# photodiode_front.net
KiCad netlist of a schematic drawn in EAGLE
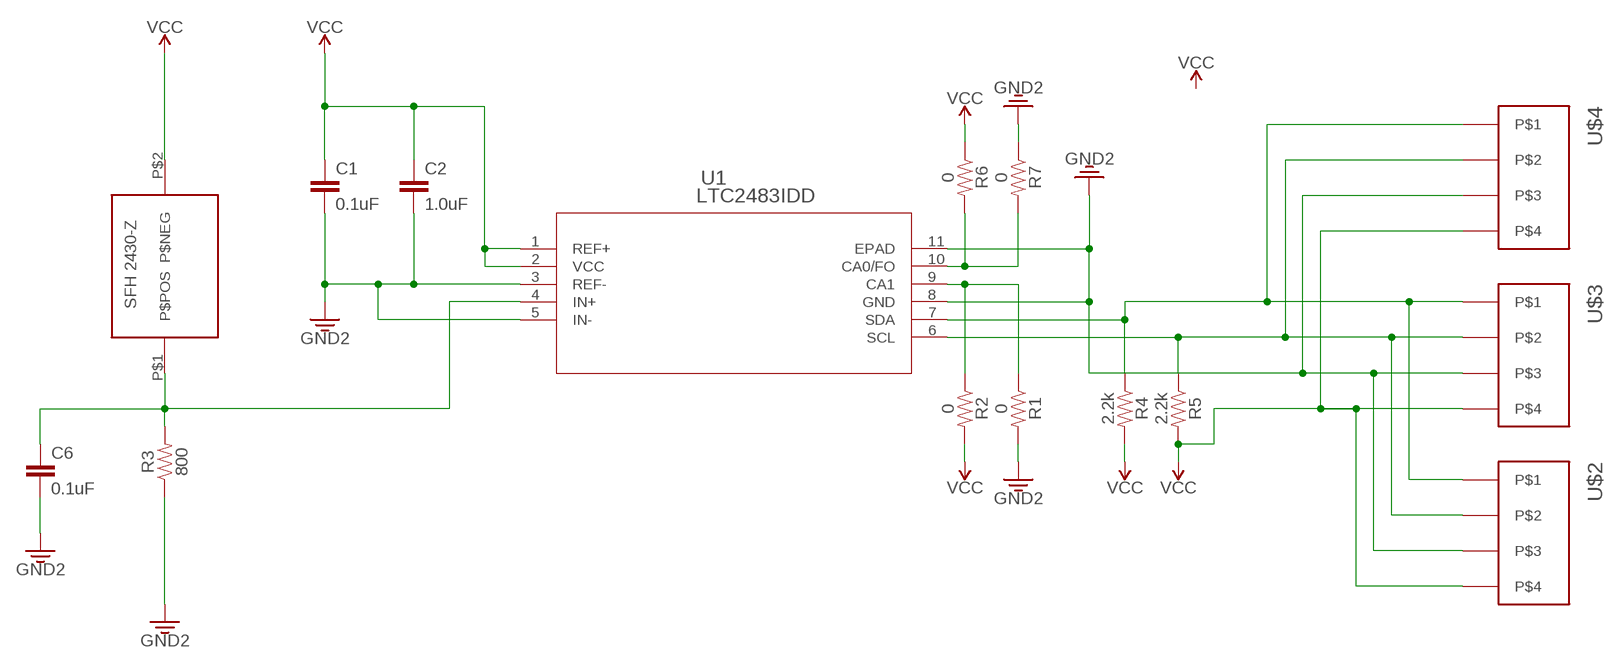
[diagram p0: schematic, sheet 1]

(export (version "E")
  (design (tool "Eeschema 10.0.6"))
  (components
    (comp (ref "C1")
      (value "0.1uF")
      (footprint "eagle-import:0805")
      (libsource (lib "eagle-import") (part "10UF-0805-10V-10%"))
    )
    (comp (ref "C2")
      (value "1.0uF")
      (footprint "eagle-import:0805")
      (libsource (lib "eagle-import") (part "10UF-0805-10V-10%"))
    )
    (comp (ref "C6")
      (value "0.1uF")
      (footprint "eagle-import:0805")
      (libsource (lib "eagle-import") (part "10UF-0805-10V-10%"))
    )
    (comp (ref "R1")
      (value "0")
      (footprint "eagle-import:0805")
      (libsource (lib "eagle-import") (part "RESISTOR0805"))
    )
    (comp (ref "R2")
      (value "0")
      (footprint "eagle-import:0805")
      (libsource (lib "eagle-import") (part "RESISTOR0805"))
    )
    (comp (ref "R3")
      (value "800")
      (footprint "eagle-import:0805")
      (libsource (lib "eagle-import") (part "RESISTOR0805"))
    )
    (comp (ref "R4")
      (value "2.2k")
      (footprint "eagle-import:0805")
      (libsource (lib "eagle-import") (part "RESISTOR0805"))
    )
    (comp (ref "R5")
      (value "2.2k")
      (footprint "eagle-import:0805")
      (libsource (lib "eagle-import") (part "RESISTOR0805"))
    )
    (comp (ref "R6")
      (value "0")
      (footprint "eagle-import:0805")
      (libsource (lib "eagle-import") (part "RESISTOR0805"))
    )
    (comp (ref "R7")
      (value "0")
      (footprint "eagle-import:0805")
      (libsource (lib "eagle-import") (part "RESISTOR0805"))
    )
    (comp (ref "U$1")
      (value "SFH-2430-Z")
      (footprint "eagle-import:DIL")
      (libsource (lib "eagle-import") (part "SFH-2430-Z"))
    )
    (comp (ref "U$2")
      (value "PICOLOCK_4PICOLOCK_4")
      (footprint "eagle-import:PICOLOCK_4")
      (libsource (lib "eagle-import") (part "PICOLOCK_4PICOLOCK_4"))
    )
    (comp (ref "U$3")
      (value "PICOLOCK_4PICOLOCK_4")
      (footprint "eagle-import:PICOLOCK_4")
      (libsource (lib "eagle-import") (part "PICOLOCK_4PICOLOCK_4"))
    )
    (comp (ref "U$4")
      (value "PICOLOCK_4PICOLOCK_4")
      (footprint "eagle-import:PICOLOCK_4")
      (libsource (lib "eagle-import") (part "PICOLOCK_4PICOLOCK_4"))
    )
    (comp (ref "U1")
      (value "LTC2483IDD")
      (footprint "eagle-import:DFN-10_DD")
      (fields (field (name "MANUFACTURER_PART_NUMBER") "ltc2483idd"))
      (libsource (lib "eagle-import") (part "LTC2483IDD"))
    )
  )
  (nets
    (net (code "1") (name "GND2") (class "Default")
      (node (ref "C1") (pin "2") (pinfunction "2_2") (pintype "passive"))
      (node (ref "C2") (pin "2") (pinfunction "2_2") (pintype "passive"))
      (node (ref "C6") (pin "2") (pinfunction "2_2") (pintype "passive"))
      (node (ref "R1") (pin "2") (pinfunction "2_2") (pintype "passive"))
      (node (ref "R3") (pin "1") (pinfunction "1_1") (pintype "passive"))
      (node (ref "R7") (pin "1") (pinfunction "1_1") (pintype "passive"))
      (node (ref "U$2") (pin "P$3") (pinfunction "P$3_P$3") (pintype "bidirectional"))
      (node (ref "U$3") (pin "P$3") (pinfunction "P$3_P$3") (pintype "bidirectional"))
      (node (ref "U$4") (pin "P$3") (pinfunction "P$3_P$3") (pintype "bidirectional"))
      (node (ref "U1") (pin "11") (pinfunction "EPAD_11") (pintype "passive"))
      (node (ref "U1") (pin "3") (pinfunction "REF-_3") (pintype "input"))
      (node (ref "U1") (pin "5") (pinfunction "IN-_5") (pintype "input"))
      (node (ref "U1") (pin "8") (pinfunction "GND_8") (pintype "power_in"))
    )
    (net (code "2") (name "Net-(U$1-P$POS)") (class "Default")
      (node (ref "C6") (pin "1") (pinfunction "1_1") (pintype "passive"))
      (node (ref "R3") (pin "2") (pinfunction "2_2") (pintype "passive"))
      (node (ref "U$1") (pin "P$1") (pinfunction "P$POS_P$1") (pintype "input"))
      (node (ref "U1") (pin "4") (pinfunction "IN+_4") (pintype "input"))
    )
    (net (code "3") (name "Net-(U1-CA0{slash}FO)") (class "Default")
      (node (ref "R6") (pin "2") (pinfunction "2_2") (pintype "passive"))
      (node (ref "R7") (pin "2") (pinfunction "2_2") (pintype "passive"))
      (node (ref "U1") (pin "10") (pinfunction "CA0/FO_10") (pintype "passive"))
    )
    (net (code "4") (name "Net-(U1-CA1)") (class "Default")
      (node (ref "R1") (pin "1") (pinfunction "1_1") (pintype "passive"))
      (node (ref "R2") (pin "1") (pinfunction "1_1") (pintype "passive"))
      (node (ref "U1") (pin "9") (pinfunction "CA1_9") (pintype "passive"))
    )
    (net (code "5") (name "Net-(U1-SCL)") (class "Default")
      (node (ref "R5") (pin "1") (pinfunction "1_1") (pintype "passive"))
      (node (ref "U$2") (pin "P$2") (pinfunction "P$2_P$2") (pintype "bidirectional"))
      (node (ref "U$3") (pin "P$2") (pinfunction "P$2_P$2") (pintype "bidirectional"))
      (node (ref "U$4") (pin "P$2") (pinfunction "P$2_P$2") (pintype "bidirectional"))
      (node (ref "U1") (pin "6") (pinfunction "SCL_6") (pintype "passive"))
    )
    (net (code "6") (name "Net-(U1-SDA)") (class "Default")
      (node (ref "R4") (pin "1") (pinfunction "1_1") (pintype "passive"))
      (node (ref "U$2") (pin "P$1") (pinfunction "P$1_P$1") (pintype "bidirectional"))
      (node (ref "U$3") (pin "P$1") (pinfunction "P$1_P$1") (pintype "bidirectional"))
      (node (ref "U$4") (pin "P$1") (pinfunction "P$1_P$1") (pintype "bidirectional"))
      (node (ref "U1") (pin "7") (pinfunction "SDA_7") (pintype "output"))
    )
    (net (code "7") (name "VCC") (class "Default")
      (node (ref "C1") (pin "1") (pinfunction "1_1") (pintype "passive"))
      (node (ref "C2") (pin "1") (pinfunction "1_1") (pintype "passive"))
      (node (ref "R2") (pin "2") (pinfunction "2_2") (pintype "passive"))
      (node (ref "R4") (pin "2") (pinfunction "2_2") (pintype "passive"))
      (node (ref "R5") (pin "2") (pinfunction "2_2") (pintype "passive"))
      (node (ref "R6") (pin "1") (pinfunction "1_1") (pintype "passive"))
      (node (ref "U$1") (pin "P$2") (pinfunction "P$NEG_P$2") (pintype "output"))
      (node (ref "U$2") (pin "P$4") (pinfunction "P$4_P$4") (pintype "bidirectional"))
      (node (ref "U$3") (pin "P$4") (pinfunction "P$4_P$4") (pintype "bidirectional"))
      (node (ref "U$4") (pin "P$4") (pinfunction "P$4_P$4") (pintype "bidirectional"))
      (node (ref "U1") (pin "1") (pinfunction "REF+_1") (pintype "input"))
      (node (ref "U1") (pin "2") (pinfunction "VCC_2") (pintype "power_in"))
    )
  )
)
